# Recepteur.net
KiCad netlist of a schematic drawn in Altium Designer
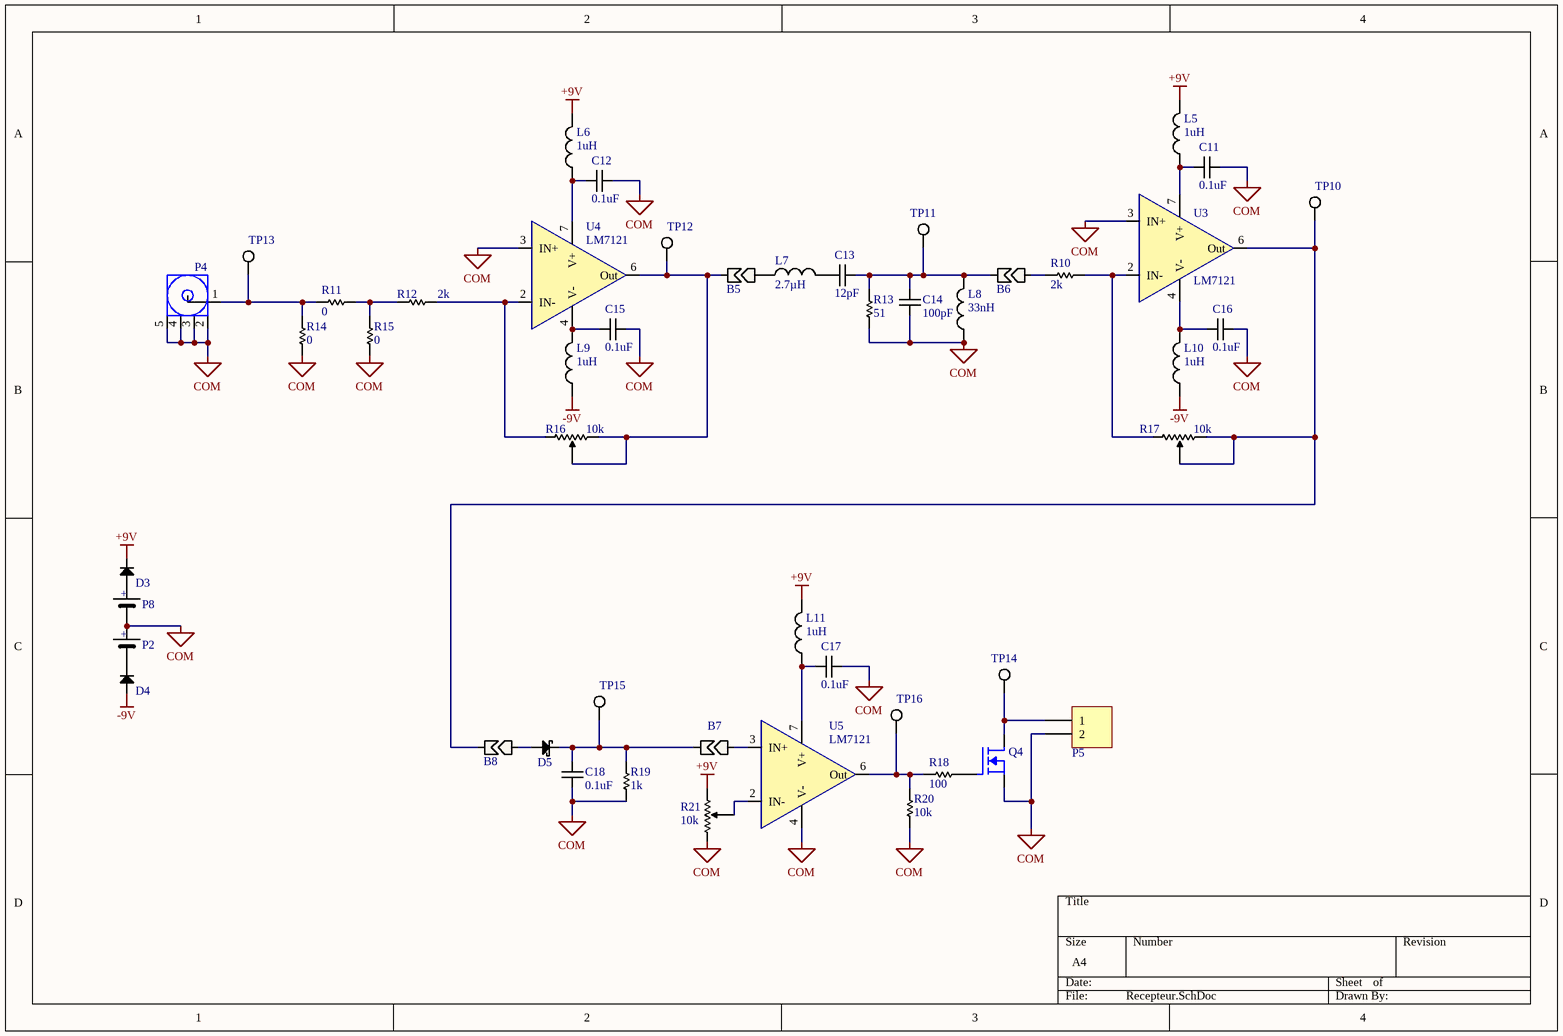
[diagram p0: Recepteur.SchDoc]

(export (version "E")
  (design (tool "Eeschema 10.0.6"))
  (components
    (comp (ref "B5")
      (value "BRIDGE")
      (footprint "BRIDGE_SMALL")
      (description "Solder Jumper Bridge")
      (fields (field (name "PART NUMBER") "Jumper-solder") (field (name "CREATED BY") "Fred"))
      (libsource (lib "local") (part "BRIDGE"))
    )
    (comp (ref "B6")
      (value "BRIDGE")
      (footprint "BRIDGE_SMALL")
      (description "Solder Jumper Bridge")
      (fields (field (name "PART NUMBER") "Jumper-solder") (field (name "CREATED BY") "Fred"))
      (libsource (lib "local") (part "BRIDGE"))
    )
    (comp (ref "B7")
      (value "BRIDGE")
      (footprint "BRIDGE_SMALL")
      (description "Solder Jumper Bridge")
      (fields (field (name "PART NUMBER") "Jumper-solder") (field (name "CREATED BY") "Fred"))
      (libsource (lib "local") (part "BRIDGE"))
    )
    (comp (ref "B8")
      (value "BRIDGE")
      (footprint "BRIDGE_SMALL")
      (description "Solder Jumper Bridge")
      (fields (field (name "PART NUMBER") "Jumper-solder") (field (name "CREATED BY") "Fred"))
      (libsource (lib "local") (part "BRIDGE"))
    )
    (comp (ref "C11")
      (value "0.1uF")
      (footprint "0805 - Cap Non-Polarized")
      (description "CAP CER 0.1UF 100V 10% X7R 0805")
      (fields
        (field (name "PART NUMBER") "Cap-TDK-CGA-0.1uF-0805")
        (field (name "MANUFACTURER") "TDK")
        (field (name "CREATED BY") "Pier-Yves")
      )
      (libsource (lib "local") (part "Cap"))
    )
    (comp (ref "C12")
      (value "0.1uF")
      (footprint "0805 - Cap Non-Polarized")
      (description "CAP CER 0.1UF 100V 10% X7R 0805")
      (fields
        (field (name "PART NUMBER") "Cap-TDK-CGA-0.1uF-0805")
        (field (name "MANUFACTURER") "TDK")
        (field (name "CREATED BY") "Pier-Yves")
      )
      (libsource (lib "local") (part "Cap"))
    )
    (comp (ref "C13")
      (value "12pF")
      (footprint "0805 - Cap Non-Polarized")
      (description "CAP CER 12PF 100V 5% NP0 0603")
      (fields
        (field (name "PART NUMBER") "Cap-TDK-CGA-12pF-0805")
        (field (name "MANUFACTURER") "TDK")
        (field (name "CREATED BY") "Pier-Yves")
      )
      (libsource (lib "local") (part "Cap"))
    )
    (comp (ref "C14")
      (value "100pF")
      (footprint "0805 - Cap Non-Polarized")
      (description "CAP CER 100PF 100V 5% NP0 0805")
      (fields
        (field (name "PART NUMBER") "Cap-TDK-CGA-100pF-0805")
        (field (name "MANUFACTURER") "TDK")
        (field (name "CREATED BY") "Pier-Yves")
      )
      (libsource (lib "local") (part "Cap"))
    )
    (comp (ref "C15")
      (value "0.1uF")
      (footprint "0805 - Cap Non-Polarized")
      (description "CAP CER 0.1UF 100V 10% X7R 0805")
      (fields
        (field (name "PART NUMBER") "Cap-TDK-CGA-0.1uF-0805")
        (field (name "MANUFACTURER") "TDK")
        (field (name "CREATED BY") "Pier-Yves")
      )
      (libsource (lib "local") (part "Cap"))
    )
    (comp (ref "C16")
      (value "0.1uF")
      (footprint "0805 - Cap Non-Polarized")
      (description "CAP CER 0.1UF 100V 10% X7R 0805")
      (fields
        (field (name "PART NUMBER") "Cap-TDK-CGA-0.1uF-0805")
        (field (name "MANUFACTURER") "TDK")
        (field (name "CREATED BY") "Pier-Yves")
      )
      (libsource (lib "local") (part "Cap"))
    )
    (comp (ref "C17")
      (value "0.1uF")
      (footprint "0805 - Cap Non-Polarized")
      (description "CAP CER 0.1UF 100V 10% X7R 0805")
      (fields
        (field (name "PART NUMBER") "Cap-TDK-CGA-0.1uF-0805")
        (field (name "MANUFACTURER") "TDK")
        (field (name "CREATED BY") "Pier-Yves")
      )
      (libsource (lib "local") (part "Cap"))
    )
    (comp (ref "C18")
      (value "0.1uF")
      (footprint "0805 - Cap Non-Polarized")
      (description "CAP CER 0.1UF 100V 10% X7R 0805")
      (fields
        (field (name "PART NUMBER") "Cap-TDK-CGA-0.1uF-0805")
        (field (name "MANUFACTURER") "TDK")
        (field (name "CREATED BY") "Pier-Yves")
      )
      (libsource (lib "local") (part "Cap"))
    )
    (comp (ref "D3")
      (value "Diode")
      (footprint "DOS-214AC (SMA)")
      (description "DIODE GEN PURPOSE 1000V 1A SMA")
      (fields
        (field (name "PART NUMBER") "S1M-13-F")
        (field (name "MANUFACTURER") "Diodes Inc.")
        (field (name "CREATED BY") "Pier-Yves")
      )
      (libsource (lib "local") (part "Diode"))
    )
    (comp (ref "D4")
      (value "Diode")
      (footprint "DOS-214AC (SMA)")
      (description "DIODE GEN PURPOSE 1000V 1A SMA")
      (fields
        (field (name "PART NUMBER") "S1M-13-F")
        (field (name "MANUFACTURER") "Diodes Inc.")
        (field (name "CREATED BY") "Pier-Yves")
      )
      (libsource (lib "local") (part "Diode"))
    )
    (comp (ref "D5")
      (value "Diode Schottky")
      (footprint "SMBflat")
      (description "DIODE SCHOTTKY 40V 2A SMBFLAT")
      (fields
        (field (name "PART NUMBER") "STPS2L40UF")
        (field (name "MANUFACTURER") "STMicroelectronics")
        (field (name "CREATED BY") "Pier-Yves")
      )
      (libsource (lib "local") (part "Diode Schottky"))
    )
    (comp (ref "L5")
      (value "1uH")
      (footprint "1008 - INDUCTOR")
      (description "IND 1000NH 370MA SRF 290MHZ 1008")
      (fields
        (field (name "PART NUMBER") "Murata-LQW2UA-Ind-AirCore-1uH")
        (field (name "MANUFACTURER") "Murata Electronics North America")
        (field (name "CREATED BY") "Frederic")
      )
      (libsource (lib "local") (part "Inductor"))
    )
    (comp (ref "L6")
      (value "1uH")
      (footprint "1008 - INDUCTOR")
      (description "IND 1000NH 370MA SRF 290MHZ 1008")
      (fields
        (field (name "PART NUMBER") "Murata-LQW2UA-Ind-AirCore-1uH")
        (field (name "MANUFACTURER") "Murata Electronics North America")
        (field (name "CREATED BY") "Frederic")
      )
      (libsource (lib "local") (part "Inductor"))
    )
    (comp (ref "L7")
      (value "2.7µH")
      (footprint "1812 - Inductor")
      (description "INDUCTOR 2.7 UH 10% 1812 SMD")
      (fields
        (field (name "PART NUMBER") "Ind-Panasonic-FB-2.7µH-1812")
        (field (name "MANUFACTURER") "Panasonic Electronic Components")
        (field (name "CREATED BY") "Pier-Yves")
      )
      (libsource (lib "local") (part "Inductor"))
    )
    (comp (ref "L8")
      (value "33nH")
      (footprint "1008 - INDUCTOR")
      (description "IND 33NH 1000MA SRF 1600MHZ 1008")
      (fields
        (field (name "PART NUMBER") "Murata-LQW2UA-Ind-AirCore-33nH")
        (field (name "MANUFACTURER") "Murata Electronics North America")
        (field (name "CREATED BY") "Frederic")
      )
      (libsource (lib "local") (part "Inductor"))
    )
    (comp (ref "L9")
      (value "1uH")
      (footprint "1008 - INDUCTOR")
      (description "IND 1000NH 370MA SRF 290MHZ 1008")
      (fields
        (field (name "PART NUMBER") "Murata-LQW2UA-Ind-AirCore-1uH")
        (field (name "MANUFACTURER") "Murata Electronics North America")
        (field (name "CREATED BY") "Frederic")
      )
      (libsource (lib "local") (part "Inductor"))
    )
    (comp (ref "L10")
      (value "1uH")
      (footprint "1008 - INDUCTOR")
      (description "IND 1000NH 370MA SRF 290MHZ 1008")
      (fields
        (field (name "PART NUMBER") "Murata-LQW2UA-Ind-AirCore-1uH")
        (field (name "MANUFACTURER") "Murata Electronics North America")
        (field (name "CREATED BY") "Frederic")
      )
      (libsource (lib "local") (part "Inductor"))
    )
    (comp (ref "L11")
      (value "1uH")
      (footprint "1008 - INDUCTOR")
      (description "IND 1000NH 370MA SRF 290MHZ 1008")
      (fields
        (field (name "PART NUMBER") "Murata-LQW2UA-Ind-AirCore-1uH")
        (field (name "MANUFACTURER") "Murata Electronics North America")
        (field (name "CREATED BY") "Frederic")
      )
      (libsource (lib "local") (part "Inductor"))
    )
    (comp (ref "P2")
      (value "Battery Holder")
      (footprint "Battery Holder - 9V - THT")
      (description "HOLDER BATTERY 9V PC MOUNT")
      (fields
        (field (name "PART NUMBER") "Battery Holder-9V-THT-Open")
        (field (name "MANUFACTURER") "MPD")
        (field (name "CREATED BY") "Pier-Yves")
      )
      (libsource (lib "local") (part "Battery"))
    )
    (comp (ref "P4")
      (value "Coax-F")
      (footprint "Coax-BNC-THT-Vertical")
      (description "CONN BNC JACK STR 50 OHM PCB")
      (fields
        (field (name "PART NUMBER") "coax-bnc-tht-vertical")
        (field (name "MANUFACTURER") "TE Connectivity")
        (field (name "CREATED BY") "Pier-Yves")
      )
      (libsource (lib "local") (part "COAX-F"))
    )
    (comp (ref "P5")
      (value "Header 1X2")
      (footprint "Headers - 1x2 - R/A - Lock")
      (fields
        (field (name "PART NUMBER") "Header-0.100-R/A-Lock-1X2")
        (field (name "MANUFACTURER") "Molex Inc.")
        (field (name "PUBLISHER") "Altium Limited")
        (field (name "CREATED BY") "Pier-Yves")
      )
      (libsource (lib "local") (part "Header 1X2"))
    )
    (comp (ref "P8")
      (value "Battery Holder")
      (footprint "Battery Holder - 9V - THT")
      (description "HOLDER BATTERY 9V PC MOUNT")
      (fields
        (field (name "PART NUMBER") "Battery Holder-9V-THT-Open")
        (field (name "MANUFACTURER") "MPD")
        (field (name "CREATED BY") "Pier-Yves")
      )
      (libsource (lib "local") (part "Battery"))
    )
    (comp (ref "Q4")
      (value "MOSFET_N")
      (footprint "SOT23-3")
      (description "MosFET Channel-N SOT-23-3 3.3A")
      (fields
        (field (name "PART NUMBER") "2N7002")
        (field (name "MANUFACTURER") "Vishay Siliconix")
        (field (name "CREATED BY") "Pier-Yves")
      )
      (libsource (lib "local") (part "MOSFET_N_GSD"))
    )
    (comp (ref "R10")
      (value "2k")
      (footprint "0805 - Resistor")
      (description "RES 2.0K OHM 1/8W 5% 0805 SMD")
      (fields
        (field (name "PART NUMBER") "Yagao-RC0805-2k")
        (field (name "MANUFACTURER") "Yagao")
        (field (name "CREATED BY") "Pier-Yves")
      )
      (libsource (lib "local") (part "Res"))
    )
    (comp (ref "R11")
      (value "0")
      (footprint "0805 - Resistor")
      (description "RES 0.0 OHM 1/8W JUMP 0805")
      (fields
        (field (name "PART NUMBER") "Jumper-0805")
        (field (name "MANUFACTURER") "Stackpole electronic")
        (field (name "CREATED BY") "Pier-Yves")
      )
      (libsource (lib "local") (part "Res"))
    )
    (comp (ref "R12")
      (value "2k")
      (footprint "0805 - Resistor")
      (description "RES 2.0K OHM 1/8W 5% 0805 SMD")
      (fields
        (field (name "PART NUMBER") "Yagao-RC0805-2k")
        (field (name "MANUFACTURER") "Yagao")
        (field (name "CREATED BY") "Pier-Yves")
      )
      (libsource (lib "local") (part "Res"))
    )
    (comp (ref "R13")
      (value "51")
      (footprint "0805 - Resistor")
      (description "RES 51 OHM 1/8W 5% 0805 SMD")
      (fields
        (field (name "PART NUMBER") "Yagao-RC0805-51")
        (field (name "MANUFACTURER") "Yagao")
        (field (name "CREATED BY") "Pier-Yves")
      )
      (libsource (lib "local") (part "Res"))
    )
    (comp (ref "R14")
      (value "0")
      (footprint "0805 - Resistor")
      (description "RES 0.0 OHM 1/8W JUMP 0805")
      (fields
        (field (name "PART NUMBER") "Jumper-0805")
        (field (name "MANUFACTURER") "Stackpole electronic")
        (field (name "CREATED BY") "Pier-Yves")
      )
      (libsource (lib "local") (part "Res"))
    )
    (comp (ref "R15")
      (value "0")
      (footprint "0805 - Resistor")
      (description "RES 0.0 OHM 1/8W JUMP 0805")
      (fields
        (field (name "PART NUMBER") "Jumper-0805")
        (field (name "MANUFACTURER") "Stackpole electronic")
        (field (name "CREATED BY") "Pier-Yves")
      )
      (libsource (lib "local") (part "Res"))
    )
    (comp (ref "R16")
      (value "10k")
      (footprint "TT-67Y")
      (description "TRIMMER 10K OHM 0.5W TH")
      (fields
        (field (name "PART NUMBER") "Pot-TT67Y-20Turns-THT-10%-10k")
        (field (name "MANUFACTURER") "TT Electronics")
        (field (name "CREATED BY") "Pier-Yves")
      )
      (libsource (lib "local") (part "Pot_wiper2"))
    )
    (comp (ref "R17")
      (value "10k")
      (footprint "TT-67Y")
      (description "TRIMMER 10K OHM 0.5W TH")
      (fields
        (field (name "PART NUMBER") "Pot-TT67Y-20Turns-THT-10%-10k")
        (field (name "MANUFACTURER") "TT Electronics")
        (field (name "CREATED BY") "Pier-Yves")
      )
      (libsource (lib "local") (part "Pot_wiper2"))
    )
    (comp (ref "R18")
      (value "100")
      (footprint "0805 - Resistor")
      (description "RES 100 OHM 1/8W 5% 0805 SMD")
      (fields
        (field (name "PART NUMBER") "Yagao-RC0805-100")
        (field (name "MANUFACTURER") "Yagao")
        (field (name "CREATED BY") "Pier-Yves")
      )
      (libsource (lib "local") (part "Res"))
    )
    (comp (ref "R19")
      (value "1k")
      (footprint "0805 - Resistor")
      (description "RES 1.0K OHM 1/8W 5% 0805 SMD")
      (fields
        (field (name "PART NUMBER") "Yagao-RC0805-1k")
        (field (name "MANUFACTURER") "Yagao")
        (field (name "CREATED BY") "Pier-Yves")
      )
      (libsource (lib "local") (part "Res"))
    )
    (comp (ref "R20")
      (value "10k")
      (footprint "0805 - Resistor")
      (description "RES 10K OHM 1/8W 5% 0805 SMD")
      (fields
        (field (name "PART NUMBER") "Yagao-RC0805-10k")
        (field (name "MANUFACTURER") "Yagao")
        (field (name "CREATED BY") "Pier-Yves")
      )
      (libsource (lib "local") (part "Res"))
    )
    (comp (ref "R21")
      (value "10k")
      (footprint "TT-67Y")
      (description "TRIMMER 10K OHM 0.5W TH")
      (fields
        (field (name "PART NUMBER") "Pot-TT67Y-20Turns-THT-10%-10k")
        (field (name "MANUFACTURER") "TT Electronics")
        (field (name "CREATED BY") "Pier-Yves")
      )
      (libsource (lib "local") (part "Pot_wiper2"))
    )
    (comp (ref "TP10")
      (value "TP")
      (footprint "TP-THT-Vertical-1")
      (description "TEST POINT PC COMPACT .063\"D BLK")
      (fields
        (field (name "PART NUMBER") "TP-THT-Vertical-1")
        (field (name "MANUFACTURER") "Keystone Electronics")
        (field (name "CREATED BY") "Pier-Yves")
      )
      (libsource (lib "local") (part "TP1"))
    )
    (comp (ref "TP11")
      (value "TP")
      (footprint "TP-THT-Vertical-1")
      (description "TEST POINT PC COMPACT .063\"D BLK")
      (fields
        (field (name "PART NUMBER") "TP-THT-Vertical-1")
        (field (name "MANUFACTURER") "Keystone Electronics")
        (field (name "CREATED BY") "Pier-Yves")
      )
      (libsource (lib "local") (part "TP1"))
    )
    (comp (ref "TP12")
      (value "TP")
      (footprint "TP-THT-Vertical-1")
      (description "TEST POINT PC COMPACT .063\"D BLK")
      (fields
        (field (name "PART NUMBER") "TP-THT-Vertical-1")
        (field (name "MANUFACTURER") "Keystone Electronics")
        (field (name "CREATED BY") "Pier-Yves")
      )
      (libsource (lib "local") (part "TP1"))
    )
    (comp (ref "TP13")
      (value "TP")
      (footprint "TP-THT-Vertical-1")
      (description "TEST POINT PC COMPACT .063\"D BLK")
      (fields
        (field (name "PART NUMBER") "TP-THT-Vertical-1")
        (field (name "MANUFACTURER") "Keystone Electronics")
        (field (name "CREATED BY") "Pier-Yves")
      )
      (libsource (lib "local") (part "TP1"))
    )
    (comp (ref "TP14")
      (value "TP")
      (footprint "TP-THT-Vertical-1")
      (description "TEST POINT PC COMPACT .063\"D BLK")
      (fields
        (field (name "PART NUMBER") "TP-THT-Vertical-1")
        (field (name "MANUFACTURER") "Keystone Electronics")
        (field (name "CREATED BY") "Pier-Yves")
      )
      (libsource (lib "local") (part "TP1"))
    )
    (comp (ref "TP15")
      (value "TP")
      (footprint "TP-THT-Vertical-1")
      (description "TEST POINT PC COMPACT .063\"D BLK")
      (fields
        (field (name "PART NUMBER") "TP-THT-Vertical-1")
        (field (name "MANUFACTURER") "Keystone Electronics")
        (field (name "CREATED BY") "Pier-Yves")
      )
      (libsource (lib "local") (part "TP1"))
    )
    (comp (ref "TP16")
      (value "TP")
      (footprint "TP-THT-Vertical-1")
      (description "TEST POINT PC COMPACT .063\"D BLK")
      (fields
        (field (name "PART NUMBER") "TP-THT-Vertical-1")
        (field (name "MANUFACTURER") "Keystone Electronics")
        (field (name "CREATED BY") "Pier-Yves")
      )
      (libsource (lib "local") (part "TP1"))
    )
    (comp (ref "U3")
      (value "LM7121")
      (footprint "SOIC8 - 0.150")
      (description "IC OPAMP VFB 175MHZ 8SOIC")
      (fields
        (field (name "PART NUMBER") "LM7121-8SOIC")
        (field (name "MANUFACTURER") "Texas Instrument")
        (field (name "CREATED BY") "Pier-Yves")
      )
      (libsource (lib "local") (part "LM7121"))
    )
    (comp (ref "U4")
      (value "LM7121")
      (footprint "SOIC8 - 0.150")
      (description "IC OPAMP VFB 175MHZ 8SOIC")
      (fields
        (field (name "PART NUMBER") "LM7121-8SOIC")
        (field (name "MANUFACTURER") "Texas Instrument")
        (field (name "CREATED BY") "Pier-Yves")
      )
      (libsource (lib "local") (part "LM7121"))
    )
    (comp (ref "U5")
      (value "LM7121")
      (footprint "SOIC8 - 0.150")
      (description "IC OPAMP VFB 175MHZ 8SOIC")
      (fields
        (field (name "PART NUMBER") "LM7121-8SOIC")
        (field (name "MANUFACTURER") "Texas Instrument")
        (field (name "CREATED BY") "Pier-Yves")
      )
      (libsource (lib "local") (part "LM7121"))
    )
  )
  (nets
    (net (code "1") (name "+9V") (class "Default")
      (node (ref "D3") (pin "2") (pinfunction "K_2") (pintype "passive"))
      (node (ref "L11") (pin "2") (pinfunction "2_2") (pintype "passive"))
      (node (ref "L5") (pin "2") (pinfunction "2_2") (pintype "passive"))
      (node (ref "L6") (pin "2") (pinfunction "2_2") (pintype "passive"))
      (node (ref "R21") (pin "1") (pinfunction "1_1") (pintype "passive"))
    )
    (net (code "2") (name "-9V") (class "Default")
      (node (ref "D4") (pin "1") (pinfunction "A_1") (pintype "passive"))
      (node (ref "L10") (pin "1") (pinfunction "1_1") (pintype "passive"))
      (node (ref "L9") (pin "1") (pinfunction "1_1") (pintype "passive"))
    )
    (net (code "3") (name "COM") (class "Default")
      (node (ref "C11") (pin "2") (pinfunction "2_2") (pintype "passive"))
      (node (ref "C12") (pin "2") (pinfunction "2_2") (pintype "passive"))
      (node (ref "C14") (pin "1") (pinfunction "1_1") (pintype "passive"))
      (node (ref "C15") (pin "2") (pinfunction "2_2") (pintype "passive"))
      (node (ref "C16") (pin "2") (pinfunction "2_2") (pintype "passive"))
      (node (ref "C17") (pin "2") (pinfunction "2_2") (pintype "passive"))
      (node (ref "C18") (pin "1") (pinfunction "1_1") (pintype "passive"))
      (node (ref "L8") (pin "1") (pinfunction "1_1") (pintype "passive"))
      (node (ref "P2") (pin "1") (pinfunction "+_1") (pintype "passive"))
      (node (ref "P4") (pin "2") (pinfunction "GND_2") (pintype "passive"))
      (node (ref "P4") (pin "3") (pinfunction "GND_3") (pintype "passive"))
      (node (ref "P4") (pin "4") (pinfunction "GND_4") (pintype "passive"))
      (node (ref "P4") (pin "5") (pinfunction "GND_5") (pintype "passive"))
      (node (ref "P5") (pin "2") (pinfunction "2_2") (pintype "passive"))
      (node (ref "P8") (pin "2") (pinfunction "-_2") (pintype "passive"))
      (node (ref "Q4") (pin "2") (pinfunction "S_2") (pintype "passive"))
      (node (ref "R13") (pin "1") (pinfunction "1_1") (pintype "passive"))
      (node (ref "R14") (pin "1") (pinfunction "1_1") (pintype "passive"))
      (node (ref "R15") (pin "2") (pinfunction "2_2") (pintype "passive"))
      (node (ref "R19") (pin "1") (pinfunction "1_1") (pintype "passive"))
      (node (ref "R20") (pin "1") (pinfunction "1_1") (pintype "passive"))
      (node (ref "R21") (pin "3") (pinfunction "3_3") (pintype "passive"))
      (node (ref "U3") (pin "3") (pinfunction "IN+_3") (pintype "passive"))
      (node (ref "U4") (pin "3") (pinfunction "IN+_3") (pintype "passive"))
      (node (ref "U5") (pin "4") (pinfunction "V-_4") (pintype "power_in"))
    )
    (net (code "4") (name "Net-(B5-Pad2)") (class "Default")
      (node (ref "B5") (pin "2") (pintype "passive"))
      (node (ref "L7") (pin "1") (pinfunction "1_1") (pintype "passive"))
    )
    (net (code "5") (name "Net-(B6-Pad1)") (class "Default")
      (node (ref "B6") (pin "1") (pintype "passive"))
      (node (ref "C13") (pin "2") (pinfunction "2_2") (pintype "passive"))
      (node (ref "C14") (pin "2") (pinfunction "2_2") (pintype "passive"))
      (node (ref "L8") (pin "2") (pinfunction "2_2") (pintype "passive"))
      (node (ref "R13") (pin "2") (pinfunction "2_2") (pintype "passive"))
      (node (ref "TP11") (pin "1") (pinfunction "1_1") (pintype "passive"))
    )
    (net (code "6") (name "Net-(B6-Pad2)") (class "Default")
      (node (ref "B6") (pin "2") (pintype "passive"))
      (node (ref "R10") (pin "2") (pinfunction "2_2") (pintype "passive"))
    )
    (net (code "7") (name "Net-(C13-Pad1)") (class "Default")
      (node (ref "C13") (pin "1") (pinfunction "1_1") (pintype "passive"))
      (node (ref "L7") (pin "2") (pinfunction "2_2") (pintype "passive"))
    )
    (net (code "8") (name "Net-(D3-A)") (class "Default")
      (node (ref "D3") (pin "1") (pinfunction "A_1") (pintype "passive"))
      (node (ref "P8") (pin "1") (pinfunction "+_1") (pintype "passive"))
    )
    (net (code "9") (name "Net-(D4-K)") (class "Default")
      (node (ref "D4") (pin "2") (pinfunction "K_2") (pintype "passive"))
      (node (ref "P2") (pin "2") (pinfunction "-_2") (pintype "passive"))
    )
    (net (code "10") (name "Net-(D5-A)") (class "Default")
      (node (ref "B8") (pin "2") (pintype "passive"))
      (node (ref "D5") (pin "1") (pinfunction "A_1") (pintype "passive"))
    )
    (net (code "11") (name "Net-(D5-K)") (class "Default")
      (node (ref "B7") (pin "1") (pintype "passive"))
      (node (ref "C18") (pin "2") (pinfunction "2_2") (pintype "passive"))
      (node (ref "D5") (pin "2") (pinfunction "K_2") (pintype "passive"))
      (node (ref "R19") (pin "2") (pinfunction "2_2") (pintype "passive"))
      (node (ref "TP15") (pin "1") (pinfunction "1_1") (pintype "passive"))
    )
    (net (code "12") (name "Net-(P4-Signal)") (class "Default")
      (node (ref "P4") (pin "1") (pinfunction "Signal_1") (pintype "passive"))
      (node (ref "R11") (pin "1") (pinfunction "1_1") (pintype "passive"))
      (node (ref "R14") (pin "2") (pinfunction "2_2") (pintype "passive"))
      (node (ref "TP13") (pin "1") (pinfunction "1_1") (pintype "passive"))
    )
    (net (code "13") (name "Net-(Q4-D)") (class "Default")
      (node (ref "P5") (pin "1") (pinfunction "1_1") (pintype "passive"))
      (node (ref "Q4") (pin "3") (pinfunction "D_3") (pintype "passive"))
      (node (ref "TP14") (pin "1") (pinfunction "1_1") (pintype "passive"))
    )
    (net (code "14") (name "Net-(Q4-G)") (class "Default")
      (node (ref "Q4") (pin "1") (pinfunction "G_1") (pintype "passive"))
      (node (ref "R18") (pin "1") (pinfunction "1_1") (pintype "passive"))
    )
    (net (code "15") (name "Net-(R11-Pad2)") (class "Default")
      (node (ref "R11") (pin "2") (pinfunction "2_2") (pintype "passive"))
      (node (ref "R12") (pin "2") (pinfunction "2_2") (pintype "passive"))
      (node (ref "R15") (pin "1") (pinfunction "1_1") (pintype "passive"))
    )
    (net (code "16") (name "Net-(R16-Wiper)") (class "Default")
      (node (ref "B5") (pin "1") (pintype "passive"))
      (node (ref "R16") (pin "1") (pinfunction "1_1") (pintype "passive"))
      (node (ref "R16") (pin "2") (pinfunction "Wiper_2") (pintype "passive"))
      (node (ref "TP12") (pin "1") (pinfunction "1_1") (pintype "passive"))
      (node (ref "U4") (pin "6") (pinfunction "Out_6") (pintype "passive"))
    )
    (net (code "17") (name "Net-(R17-Wiper)") (class "Default")
      (node (ref "B8") (pin "1") (pintype "passive"))
      (node (ref "R17") (pin "1") (pinfunction "1_1") (pintype "passive"))
      (node (ref "R17") (pin "2") (pinfunction "Wiper_2") (pintype "passive"))
      (node (ref "TP10") (pin "1") (pinfunction "1_1") (pintype "passive"))
      (node (ref "U3") (pin "6") (pinfunction "Out_6") (pintype "passive"))
    )
    (net (code "18") (name "Net-(R21-Wiper)") (class "Default")
      (node (ref "R21") (pin "2") (pinfunction "Wiper_2") (pintype "passive"))
      (node (ref "U5") (pin "2") (pinfunction "IN-_2") (pintype "passive"))
    )
    (net (code "19") (name "Net-(U3-IN-)") (class "Default")
      (node (ref "R10") (pin "1") (pinfunction "1_1") (pintype "passive"))
      (node (ref "R17") (pin "3") (pinfunction "3_3") (pintype "passive"))
      (node (ref "U3") (pin "2") (pinfunction "IN-_2") (pintype "passive"))
    )
    (net (code "20") (name "Net-(U3-V+)") (class "Default")
      (node (ref "C11") (pin "1") (pinfunction "1_1") (pintype "passive"))
      (node (ref "L5") (pin "1") (pinfunction "1_1") (pintype "passive"))
      (node (ref "U3") (pin "7") (pinfunction "V+_7") (pintype "power_in"))
    )
    (net (code "21") (name "Net-(U3-V-)") (class "Default")
      (node (ref "C16") (pin "1") (pinfunction "1_1") (pintype "passive"))
      (node (ref "L10") (pin "2") (pinfunction "2_2") (pintype "passive"))
      (node (ref "U3") (pin "4") (pinfunction "V-_4") (pintype "power_in"))
    )
    (net (code "22") (name "Net-(U4-IN-)") (class "Default")
      (node (ref "R12") (pin "1") (pinfunction "1_1") (pintype "passive"))
      (node (ref "R16") (pin "3") (pinfunction "3_3") (pintype "passive"))
      (node (ref "U4") (pin "2") (pinfunction "IN-_2") (pintype "passive"))
    )
    (net (code "23") (name "Net-(U4-V+)") (class "Default")
      (node (ref "C12") (pin "1") (pinfunction "1_1") (pintype "passive"))
      (node (ref "L6") (pin "1") (pinfunction "1_1") (pintype "passive"))
      (node (ref "U4") (pin "7") (pinfunction "V+_7") (pintype "power_in"))
    )
    (net (code "24") (name "Net-(U4-V-)") (class "Default")
      (node (ref "C15") (pin "1") (pinfunction "1_1") (pintype "passive"))
      (node (ref "L9") (pin "2") (pinfunction "2_2") (pintype "passive"))
      (node (ref "U4") (pin "4") (pinfunction "V-_4") (pintype "power_in"))
    )
    (net (code "25") (name "Net-(U5-IN+)") (class "Default")
      (node (ref "B7") (pin "2") (pintype "passive"))
      (node (ref "U5") (pin "3") (pinfunction "IN+_3") (pintype "passive"))
    )
    (net (code "26") (name "Net-(U5-Out)") (class "Default")
      (node (ref "R18") (pin "2") (pinfunction "2_2") (pintype "passive"))
      (node (ref "R20") (pin "2") (pinfunction "2_2") (pintype "passive"))
      (node (ref "TP16") (pin "1") (pinfunction "1_1") (pintype "passive"))
      (node (ref "U5") (pin "6") (pinfunction "Out_6") (pintype "passive"))
    )
    (net (code "27") (name "Net-(U5-V+)") (class "Default")
      (node (ref "C17") (pin "1") (pinfunction "1_1") (pintype "passive"))
      (node (ref "L11") (pin "1") (pinfunction "1_1") (pintype "passive"))
      (node (ref "U5") (pin "7") (pinfunction "V+_7") (pintype "power_in"))
    )
  )
)
